# solar_project_example.net
KiCad netlist of a schematic drawn in EAGLE
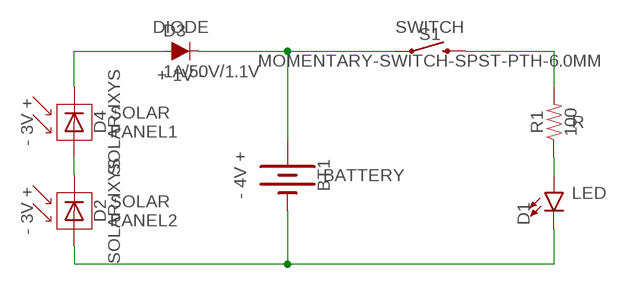
[diagram p0: schematic, sheet 1]

(export (version "E")
  (design (tool "Eeschema 10.0.6"))
  (components
    (comp (ref "BT1")
      (value "BATTERY-20MM_PTH")
      (footprint "eagle-import:BATTCOM_20MM_PTH")
      (libsource (lib "eagle-import") (part "BATTERY-20MM_PTH"))
    )
    (comp (ref "D1")
      (value "LED5MM")
      (footprint "eagle-import:LED_5MM")
      (libsource (lib "eagle-import") (part "LED5MM"))
    )
    (comp (ref "D2")
      (value "SOLAR-IXYS")
      (footprint "eagle-import:SOIC-8")
      (libsource (lib "eagle-import") (part "SOLAR-IXYS"))
    )
    (comp (ref "D3")
      (value "1A/50V/1.1V")
      (footprint "eagle-import:DIODE-1N4001")
      (libsource (lib "eagle-import") (part "DIODE-PTH"))
    )
    (comp (ref "D4")
      (value "SOLAR-IXYS")
      (footprint "eagle-import:SOIC-8")
      (libsource (lib "eagle-import") (part "SOLAR-IXYS"))
    )
    (comp (ref "R1")
      (value "100")
      (footprint "eagle-import:AXIAL-0.3")
      (libsource (lib "eagle-import") (part "100OHM-HORIZ-1/4W-1%"))
    )
    (comp (ref "S1")
      (value "MOMENTARY-SWITCH-SPST-PTH-6.0MM")
      (footprint "eagle-import:TACTILE_SWITCH_PTH_6.0MM")
      (libsource (lib "eagle-import") (part "MOMENTARY-SWITCH-SPST-PTH-6.0MM"))
    )
  )
  (nets
    (net (code "1") (name "Net-(BT1-+)") (class "Default")
      (node (ref "BT1") (pin "1") (pinfunction "+_1") (pintype "power_in"))
      (node (ref "D3") (pin "C") (pinfunction "C_C") (pintype "passive"))
      (node (ref "S1") (pin "1") (pinfunction "1_1") (pintype "passive"))
    )
    (net (code "2") (name "Net-(BT1--)") (class "Default")
      (node (ref "BT1") (pin "2") (pinfunction "-_2") (pintype "power_in"))
      (node (ref "D1") (pin "K") (pinfunction "C_K") (pintype "passive"))
      (node (ref "D2") (pin "8") (pinfunction "A_8") (pintype "passive"))
    )
    (net (code "3") (name "Net-(D2-C)") (class "Default")
      (node (ref "D2") (pin "5") (pinfunction "C_5") (pintype "passive"))
      (node (ref "D4") (pin "8") (pinfunction "A_8") (pintype "passive"))
    )
    (net (code "4") (name "Net-(D4-C)") (class "Default")
      (node (ref "D3") (pin "A") (pinfunction "A_A") (pintype "passive"))
      (node (ref "D4") (pin "5") (pinfunction "C_5") (pintype "passive"))
    )
    (net (code "5") (name "Net-(R1-1)") (class "Default")
      (node (ref "D1") (pin "A") (pinfunction "A_A") (pintype "passive"))
      (node (ref "R1") (pin "P$1") (pinfunction "1_P$1") (pintype "passive"))
    )
    (net (code "6") (name "Net-(R1-2)") (class "Default")
      (node (ref "R1") (pin "P$2") (pinfunction "2_P$2") (pintype "passive"))
      (node (ref "S1") (pin "3") (pinfunction "2_3") (pintype "passive"))
    )
  )
)
